# LampenSteuerung_Encoder.net
KiCad netlist of a schematic drawn in EAGLE
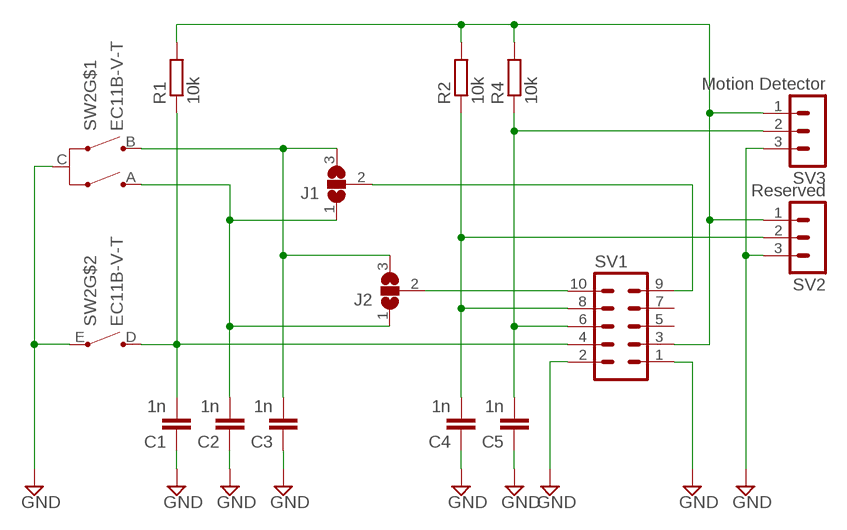
[diagram p0: schematic, sheet 1]

(export (version "E")
  (design (tool "Eeschema 10.0.6"))
  (components
    (comp (ref "C1")
      (value "1n")
      (footprint "eagle-import:C0603K")
      (libsource (lib "eagle-import") (part "C-EUC0603K"))
    )
    (comp (ref "C2")
      (value "1n")
      (footprint "eagle-import:C0603K")
      (libsource (lib "eagle-import") (part "C-EUC0603K"))
    )
    (comp (ref "C3")
      (value "1n")
      (footprint "eagle-import:C0603K")
      (libsource (lib "eagle-import") (part "C-EUC0603K"))
    )
    (comp (ref "C4")
      (value "1n")
      (footprint "eagle-import:C0603K")
      (libsource (lib "eagle-import") (part "C-EUC0603K"))
    )
    (comp (ref "C5")
      (value "1n")
      (footprint "eagle-import:C0603K")
      (libsource (lib "eagle-import") (part "C-EUC0603K"))
    )
    (comp (ref "J1")
      (value "SJ2W")
      (footprint "eagle-import:SJ_2")
      (libsource (lib "eagle-import") (part "SJ2W"))
    )
    (comp (ref "J2")
      (value "SJ2W")
      (footprint "eagle-import:SJ_2")
      (libsource (lib "eagle-import") (part "SJ2W"))
    )
    (comp (ref "R1")
      (value "10k")
      (footprint "eagle-import:R0805")
      (libsource (lib "eagle-import") (part "R-EU_R0805"))
    )
    (comp (ref "R2")
      (value "10k")
      (footprint "eagle-import:R0805")
      (libsource (lib "eagle-import") (part "R-EU_R0805"))
    )
    (comp (ref "R4")
      (value "10k")
      (footprint "eagle-import:R0805")
      (libsource (lib "eagle-import") (part "R-EU_R0805"))
    )
    (comp (ref "SV1")
      (value "MA05-2")
      (footprint "eagle-import:MA05-2")
      (libsource (lib "eagle-import") (part "MA05-2"))
    )
    (comp (ref "SV2")
      (value "Reserved")
      (footprint "eagle-import:MA03-1")
      (libsource (lib "eagle-import") (part "MA03-1"))
    )
    (comp (ref "SV3")
      (value "Motion Detector")
      (footprint "eagle-import:MA03-1")
      (libsource (lib "eagle-import") (part "MA03-1"))
    )
    (comp (ref "SW2")
      (value "EC11B-V-T")
      (footprint "eagle-import:EC11B-V")
      (libsource (lib "eagle-import") (part "EC11B-V-T"))
    )
  )
  (nets
    (net (code "1") (name "GND") (class "Default")
      (node (ref "C1") (pin "1") (pinfunction "1_1") (pintype "passive"))
      (node (ref "C2") (pin "1") (pinfunction "1_1") (pintype "passive"))
      (node (ref "C3") (pin "1") (pinfunction "1_1") (pintype "passive"))
      (node (ref "C4") (pin "1") (pinfunction "1_1") (pintype "passive"))
      (node (ref "C5") (pin "1") (pinfunction "1_1") (pintype "passive"))
      (node (ref "SV1") (pin "1") (pinfunction "1_1") (pintype "passive"))
      (node (ref "SV1") (pin "2") (pinfunction "2_2") (pintype "passive"))
      (node (ref "SV2") (pin "3") (pinfunction "3_3") (pintype "passive"))
      (node (ref "SV3") (pin "3") (pinfunction "3_3") (pintype "passive"))
      (node (ref "SW2") (pin "C") (pinfunction "C_C") (pintype "passive"))
      (node (ref "SW2") (pin "E") (pinfunction "E_E") (pintype "passive"))
    )
    (net (code "2") (name "Net-(C1-Pad2)") (class "Default")
      (node (ref "C1") (pin "2") (pinfunction "2_2") (pintype "passive"))
      (node (ref "R1") (pin "1") (pinfunction "1_1") (pintype "passive"))
      (node (ref "SV1") (pin "4") (pinfunction "4_4") (pintype "passive"))
      (node (ref "SW2") (pin "D") (pinfunction "D_D") (pintype "passive"))
    )
    (net (code "3") (name "Net-(C2-Pad2)") (class "Default")
      (node (ref "C2") (pin "2") (pinfunction "2_2") (pintype "passive"))
      (node (ref "J1") (pin "1") (pinfunction "1_1") (pintype "passive"))
      (node (ref "J2") (pin "1") (pinfunction "1_1") (pintype "passive"))
      (node (ref "SW2") (pin "A") (pinfunction "A_A") (pintype "passive"))
    )
    (net (code "4") (name "Net-(C3-Pad2)") (class "Default")
      (node (ref "C3") (pin "2") (pinfunction "2_2") (pintype "passive"))
      (node (ref "J1") (pin "3") (pinfunction "3_3") (pintype "passive"))
      (node (ref "J2") (pin "3") (pinfunction "3_3") (pintype "passive"))
      (node (ref "SW2") (pin "B") (pinfunction "B_B") (pintype "passive"))
    )
    (net (code "5") (name "Net-(C4-Pad2)") (class "Default")
      (node (ref "C4") (pin "2") (pinfunction "2_2") (pintype "passive"))
      (node (ref "R2") (pin "1") (pinfunction "1_1") (pintype "passive"))
      (node (ref "SV1") (pin "8") (pinfunction "8_8") (pintype "passive"))
      (node (ref "SV2") (pin "2") (pinfunction "2_2") (pintype "passive"))
    )
    (net (code "6") (name "Net-(C5-Pad2)") (class "Default")
      (node (ref "C5") (pin "2") (pinfunction "2_2") (pintype "passive"))
      (node (ref "R4") (pin "1") (pinfunction "1_1") (pintype "passive"))
      (node (ref "SV1") (pin "6") (pinfunction "6_6") (pintype "passive"))
      (node (ref "SV3") (pin "2") (pinfunction "2_2") (pintype "passive"))
    )
    (net (code "7") (name "Net-(J1-Pad2)") (class "Default")
      (node (ref "J1") (pin "2") (pinfunction "2_2") (pintype "passive"))
      (node (ref "SV1") (pin "9") (pinfunction "9_9") (pintype "passive"))
    )
    (net (code "8") (name "Net-(J2-Pad2)") (class "Default")
      (node (ref "J2") (pin "2") (pinfunction "2_2") (pintype "passive"))
      (node (ref "SV1") (pin "10") (pinfunction "10_10") (pintype "passive"))
    )
    (net (code "9") (name "Net-(R1-Pad2)") (class "Default")
      (node (ref "R1") (pin "2") (pinfunction "2_2") (pintype "passive"))
      (node (ref "R2") (pin "2") (pinfunction "2_2") (pintype "passive"))
      (node (ref "R4") (pin "2") (pinfunction "2_2") (pintype "passive"))
      (node (ref "SV1") (pin "3") (pinfunction "3_3") (pintype "passive"))
      (node (ref "SV2") (pin "1") (pinfunction "1_1") (pintype "passive"))
      (node (ref "SV3") (pin "1") (pinfunction "1_1") (pintype "passive"))
    )
    (net (code "10") (name "unconnected-(SV1-Pad5)") (class "Default")
      (node (ref "SV1") (pin "5") (pinfunction "5_5") (pintype "passive"))
    )
    (net (code "11") (name "unconnected-(SV1-Pad7)") (class "Default")
      (node (ref "SV1") (pin "7") (pinfunction "7_7") (pintype "passive"))
    )
  )
)
